# Chess_Clock_Touch_Panel.net
KiCad netlist of a schematic drawn in Altium Designer
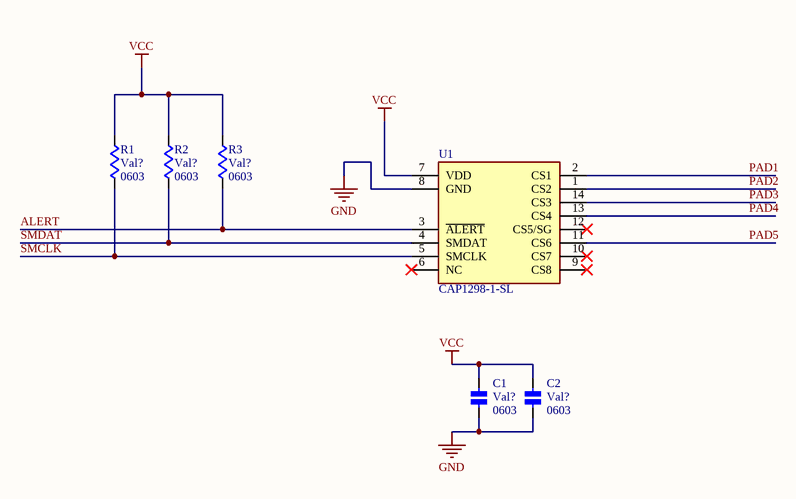
[diagram p0: Chess Clock Touch Panel.SchDoc]

(export (version "E")
  (design (tool "Eeschema 10.0.6"))
  (components
    (comp (ref "C1")
      (value "Val?")
      (footprint "CAPC0603X08N")
      (description "GENERIC CAPC 0603")
      (fields (field (name "CAPACITANCE") "Val?") (field (name "PACKAGE") "0603"))
      (libsource (lib "Chess Clock Component") (part "GENERIC CAPC 0603"))
    )
    (comp (ref "C2")
      (value "Val?")
      (footprint "CAPC0603X08N")
      (description "GENERIC CAPC 0603")
      (fields (field (name "CAPACITANCE") "Val?") (field (name "PACKAGE") "0603"))
      (libsource (lib "Chess Clock Component") (part "GENERIC CAPC 0603"))
    )
    (comp (ref "R1")
      (value "Val?")
      (footprint "RESC0603X04N")
      (description "GENERIC RESC 0603")
      (fields (field (name "RESISTANCE") "Val?") (field (name "PACKAGE") "0603"))
      (libsource (lib "Chess Clock Component") (part "GENERIC RESC 0603"))
    )
    (comp (ref "R2")
      (value "Val?")
      (footprint "RESC0603X04N")
      (description "GENERIC RESC 0603")
      (fields (field (name "RESISTANCE") "Val?") (field (name "PACKAGE") "0603"))
      (libsource (lib "Chess Clock Component") (part "GENERIC RESC 0603"))
    )
    (comp (ref "R3")
      (value "Val?")
      (footprint "RESC0603X04N")
      (description "GENERIC RESC 0603")
      (fields (field (name "RESISTANCE") "Val?") (field (name "PACKAGE") "0603"))
      (libsource (lib "Chess Clock Component") (part "GENERIC RESC 0603"))
    )
    (comp (ref "U1")
      (value "CAP1298-1-SL")
      (footprint "CAP1298-1-SL")
      (description "8-CHANNEL CAPACITIVE TOUCH SENSO")
      (fields (field (name "MANUFACTURER") "Microchip Technology"))
      (libsource (lib "Chess Clock Component") (part "CAP1298-1-SL"))
    )
  )
  (nets
    (net (code "1") (name "/ALERT") (class "Default")
      (node (ref "R3") (pin "1") (pinfunction "1_1") (pintype "passive"))
      (node (ref "U1") (pin "3") (pinfunction "~{ALERT}_3") (pintype "passive"))
    )
    (net (code "2") (name "/PAD1") (class "Default")
      (node (ref "U1") (pin "2") (pinfunction "CS1_2") (pintype "passive"))
    )
    (net (code "3") (name "/PAD2") (class "Default")
      (node (ref "U1") (pin "1") (pinfunction "CS2_1") (pintype "passive"))
    )
    (net (code "4") (name "/PAD3") (class "Default")
      (node (ref "U1") (pin "14") (pinfunction "CS3_14") (pintype "passive"))
    )
    (net (code "5") (name "/PAD4") (class "Default")
      (node (ref "U1") (pin "13") (pinfunction "CS4_13") (pintype "passive"))
    )
    (net (code "6") (name "/PAD5") (class "Default")
      (node (ref "U1") (pin "11") (pinfunction "CS6_11") (pintype "passive"))
    )
    (net (code "7") (name "/SMCLK") (class "Default")
      (node (ref "R1") (pin "1") (pinfunction "1_1") (pintype "passive"))
      (node (ref "U1") (pin "5") (pinfunction "SMCLK_5") (pintype "passive"))
    )
    (net (code "8") (name "/SMDAT") (class "Default")
      (node (ref "R2") (pin "1") (pinfunction "1_1") (pintype "passive"))
      (node (ref "U1") (pin "4") (pinfunction "SMDAT_4") (pintype "passive"))
    )
    (net (code "9") (name "GND") (class "Default")
      (node (ref "C1") (pin "2") (pinfunction "2_2") (pintype "passive"))
      (node (ref "C2") (pin "2") (pinfunction "2_2") (pintype "passive"))
      (node (ref "U1") (pin "8") (pinfunction "GND_8") (pintype "passive"))
    )
    (net (code "10") (name "VCC") (class "Default")
      (node (ref "C1") (pin "1") (pinfunction "1_1") (pintype "passive"))
      (node (ref "C2") (pin "1") (pinfunction "1_1") (pintype "passive"))
      (node (ref "R1") (pin "2") (pinfunction "2_2") (pintype "passive"))
      (node (ref "R2") (pin "2") (pinfunction "2_2") (pintype "passive"))
      (node (ref "R3") (pin "2") (pinfunction "2_2") (pintype "passive"))
      (node (ref "U1") (pin "7") (pinfunction "VDD_7") (pintype "passive"))
    )
    (net (code "11") (name "unconnected-(U1-CS5{slash}SG-Pad12)") (class "Default")
      (node (ref "U1") (pin "12") (pinfunction "CS5/SG_12") (pintype "passive+no_connect"))
    )
    (net (code "12") (name "unconnected-(U1-CS7-Pad10)") (class "Default")
      (node (ref "U1") (pin "10") (pinfunction "CS7_10") (pintype "passive+no_connect"))
    )
    (net (code "13") (name "unconnected-(U1-CS8-Pad9)") (class "Default")
      (node (ref "U1") (pin "9") (pinfunction "CS8_9") (pintype "passive+no_connect"))
    )
    (net (code "14") (name "unconnected-(U1-NC-Pad6)") (class "Default")
      (node (ref "U1") (pin "6") (pinfunction "NC_6") (pintype "passive+no_connect"))
    )
  )
)
